# MSP432P401R_Mini_System.net
KiCad netlist of a schematic drawn in Altium Designer
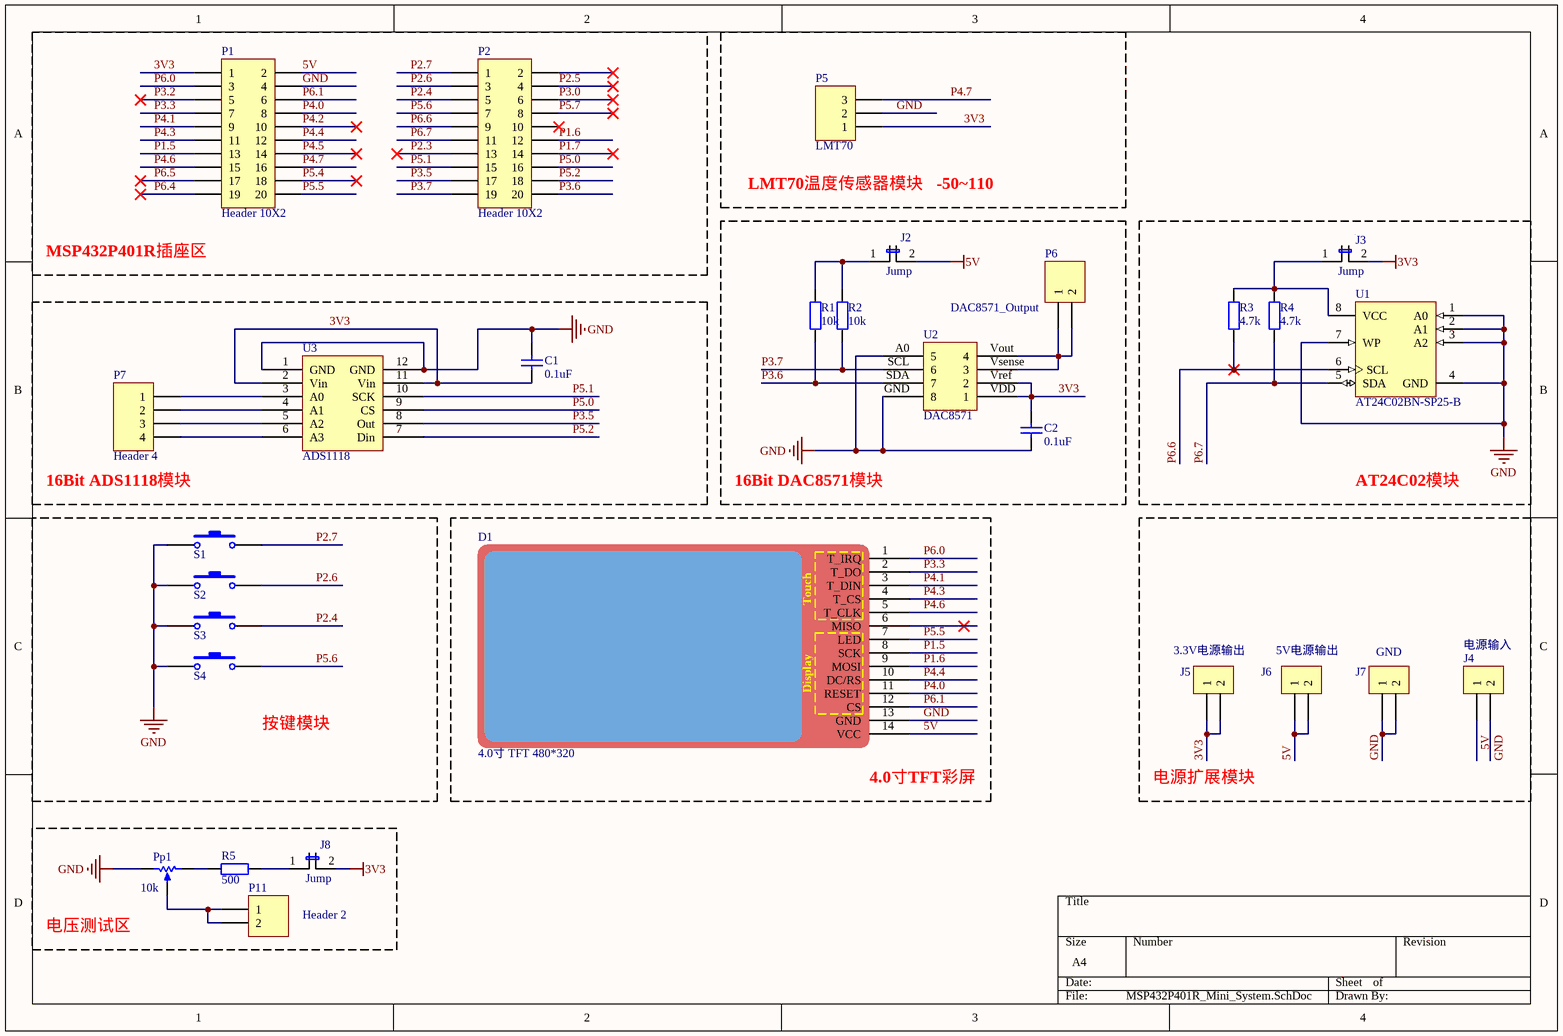
[diagram p0: MSP432P401R_Mini_System.SchDoc]

(export (version "E")
  (design (tool "Eeschema 10.0.6"))
  (components
    (comp (ref "C1")
      (value "0.1uF")
      (footprint "0805_C")
      (description "CBB聚乙烯薄膜电容")
      (fields (field (name "VOLTAGE") "63V") (field (name "PUBLISHER") "Altium Limited"))
      (libsource (lib "02-Miscellaneous_Devices_ZSF_Library") (part "Cap Nicklon"))
    )
    (comp (ref "C2")
      (value "0.1uF")
      (footprint "0805_C")
      (description "CBB聚乙烯薄膜电容")
      (fields (field (name "VOLTAGE") "63V") (field (name "PUBLISHER") "Altium Limited"))
      (libsource (lib "02-Miscellaneous_Devices_ZSF_Library") (part "Cap Nicklon"))
    )
    (comp (ref "D1")
      (value "4.0寸 TFT 480*320")
      (footprint "4.0 TFT")
      (libsource (lib "Mini_System") (part "4.0寸 TFT 480*320"))
    )
    (comp (ref "J2") (value "Jump") (footprint "Jump") (libsource (lib "Mini_System") (part "Jump")))
    (comp (ref "J3") (value "Jump") (footprint "Jump") (libsource (lib "Mini_System") (part "Jump")))
    (comp (ref "J4")
      (value "电源输入")
      (footprint "Connector:XH2.54-2P")
      (description "连接器")
      (libsource (lib "Connector") (part "CON2"))
    )
    (comp (ref "J5")
      (value "3.3V电源输出")
      (footprint "Connector:WJ500V-5.08-2")
      (description "接线端子")
      (libsource (lib "Connector") (part "KF128-5.08MM-2P"))
    )
    (comp (ref "J6")
      (value "5V电源输出")
      (footprint "Connector:WJ500V-5.08-2")
      (description "接线端子")
      (libsource (lib "Connector") (part "KF128-5.08MM-2P"))
    )
    (comp (ref "J7")
      (value "GND")
      (footprint "Connector:WJ500V-5.08-2")
      (description "接线端子")
      (libsource (lib "Connector") (part "KF128-5.08MM-2P"))
    )
    (comp (ref "J8") (value "Jump") (footprint "jump") (libsource (lib "Mini_System") (part "Jump")))
    (comp (ref "P1")
      (value "Header 10X2")
      (footprint "HDR2X10")
      (description "Header, 10-Pin, Dual row")
      (fields (field (name "PUBLISHER") "Altium Limited"))
      (libsource (lib "03-EButterflyIntegratedLibrary") (part "Header 10X2"))
    )
    (comp (ref "P2")
      (value "Header 10X2")
      (footprint "HDR2X10")
      (description "Header, 10-Pin, Dual row")
      (fields (field (name "PUBLISHER") "Altium Limited"))
      (libsource (lib "03-EButterflyIntegratedLibrary") (part "Header 10X2"))
    )
    (comp (ref "P5")
      (value "LMT70")
      (footprint "HDR-1X3_M")
      (description "Header, 3-Pin")
      (fields (field (name "PUBLISHER") "Altium Limited"))
      (libsource (lib "03-EButterflyIntegratedLibrary") (part "Header 3"))
    )
    (comp (ref "P6")
      (value "DAC8571_Output")
      (footprint "HDR-1X2_H")
      (description "Header, 2-Pin")
      (fields (field (name "PUBLISHER") "Altium Limited"))
      (libsource (lib "03-EButterflyIntegratedLibrary") (part "Header 2"))
    )
    (comp (ref "P7")
      (value "Header 4")
      (footprint "HDR1X4")
      (description "Header, 4-Pin")
      (fields (field (name "PUBLISHER") "Altium Limited"))
      (libsource (lib "03-EButterflyIntegratedLibrary") (part "Header 4"))
    )
    (comp (ref "P11")
      (value "Header 2")
      (footprint "HDR1X2")
      (description "Header, 2-Pin")
      (fields (field (name "PUBLISHER") "Altium Limited"))
      (libsource (lib "") (part "Header 2_1"))
    )
    (comp (ref "Pp1")
      (value "10k")
      (footprint "RM065")
      (description "3296电位器")
      (libsource (lib "02-Miscellaneous_Devices_ZSF_Library") (part "RP_3296"))
    )
    (comp (ref "R1")
      (value "10k")
      (footprint "Resistors:0805_R")
      (description "Resistor")
      (fields (field (name "PUBLISHER") "Altium Limited"))
      (libsource (lib "") (part "Res2_1"))
    )
    (comp (ref "R2")
      (value "10k")
      (footprint "Resistors:0805_R")
      (description "Resistor")
      (fields (field (name "PUBLISHER") "Altium Limited"))
      (libsource (lib "") (part "Res2_1"))
    )
    (comp (ref "R3")
      (value "4.7k")
      (footprint "Resistors:0805_R")
      (description "Resistor")
      (fields (field (name "PUBLISHER") "Altium Limited"))
      (libsource (lib "") (part "Res2_1"))
    )
    (comp (ref "R4")
      (value "4.7k")
      (footprint "Resistors:0805_R")
      (description "Resistor")
      (fields (field (name "PUBLISHER") "Altium Limited"))
      (libsource (lib "") (part "Res2_1"))
    )
    (comp (ref "R5")
      (value "500")
      (footprint "Resistors:0805_R")
      (description "Resistor")
      (fields (field (name "PUBLISHER") "Altium Limited"))
      (libsource (lib "Miscellaneous Devices") (part "Res2"))
    )
    (comp (ref "S1")
      (value "S1")
      (footprint "TSW SMD-3*6*4.3")
      (description "Tactile Switch触觉开关")
      (fields (field (name "PUBLISHER") "Altium Limited"))
      (libsource (lib "02-Miscellaneous_Devices_ZSF_Library") (part "SW-PB"))
    )
    (comp (ref "S2")
      (value "S2")
      (footprint "TSW SMD-3*6*4.3")
      (description "Tactile Switch触觉开关")
      (fields (field (name "PUBLISHER") "Altium Limited"))
      (libsource (lib "02-Miscellaneous_Devices_ZSF_Library") (part "SW-PB"))
    )
    (comp (ref "S3")
      (value "S3")
      (footprint "TSW SMD-3*6*4.3")
      (description "Tactile Switch触觉开关")
      (fields (field (name "PUBLISHER") "Altium Limited"))
      (libsource (lib "02-Miscellaneous_Devices_ZSF_Library") (part "SW-PB"))
    )
    (comp (ref "S4")
      (value "S4")
      (footprint "TSW SMD-3*6*4.3")
      (description "Tactile Switch触觉开关")
      (fields (field (name "PUBLISHER") "Altium Limited"))
      (libsource (lib "02-Miscellaneous_Devices_ZSF_Library") (part "SW-PB"))
    )
    (comp (ref "U1")
      (value "AT24C02BN-SP25-B")
      (footprint "DIP8-300_MH")
      (fields (field (name "PUBLISHER") "Altium Limited"))
      (libsource (lib "altium-import") (part "root_0_mirrored_AT24C02BN-SP25-B_"))
    )
    (comp (ref "U2")
      (value "DAC8571")
      (footprint "DIP8-300_MH")
      (description "16位DAC芯片，将数字量转化为模拟电压输出")
      (libsource (lib "Mini_System") (part "DAC8571"))
    )
    (comp (ref "U3")
      (value "ADS1118")
      (footprint "ADS1118")
      (description "16位ADC芯片，将模拟电压信号转化为数字信号供单片机处理")
      (libsource (lib "Mini_System") (part "ADS1118"))
    )
  )
  (nets
    (net (code "1") (name "/P1.5") (class "Default")
      (node (ref "D1") (pin "8") (pinfunction "SCK_8") (pintype "passive"))
      (node (ref "P1") (pin "13") (pinfunction "13_13") (pintype "passive"))
    )
    (net (code "2") (name "/P1.6") (class "Default")
      (node (ref "D1") (pin "9") (pinfunction "MOSI_9") (pintype "passive"))
      (node (ref "P2") (pin "12") (pinfunction "12_12") (pintype "passive"))
    )
    (net (code "3") (name "/P1.7") (class "Default")
      (node (ref "P2") (pin "14") (pinfunction "14_14") (pintype "passive+no_connect"))
    )
    (net (code "4") (name "/P2.3") (class "Default")
      (node (ref "P2") (pin "13") (pinfunction "13_13") (pintype "passive+no_connect"))
    )
    (net (code "5") (name "/P2.4") (class "Default")
      (node (ref "P2") (pin "5") (pinfunction "5_5") (pintype "passive"))
      (node (ref "S3") (pin "2") (pinfunction "2_2") (pintype "passive"))
    )
    (net (code "6") (name "/P2.5") (class "Default")
      (node (ref "P2") (pin "4") (pinfunction "4_4") (pintype "passive+no_connect"))
    )
    (net (code "7") (name "/P2.6") (class "Default")
      (node (ref "P2") (pin "3") (pinfunction "3_3") (pintype "passive"))
      (node (ref "S2") (pin "2") (pinfunction "2_2") (pintype "passive"))
    )
    (net (code "8") (name "/P2.7") (class "Default")
      (node (ref "P2") (pin "1") (pinfunction "1_1") (pintype "passive"))
      (node (ref "S1") (pin "2") (pinfunction "2_2") (pintype "passive"))
    )
    (net (code "9") (name "/P3.0") (class "Default")
      (node (ref "P2") (pin "6") (pinfunction "6_6") (pintype "passive+no_connect"))
    )
    (net (code "10") (name "/P3.2") (class "Default")
      (node (ref "P1") (pin "5") (pinfunction "5_5") (pintype "passive+no_connect"))
    )
    (net (code "11") (name "/P3.3") (class "Default")
      (node (ref "D1") (pin "2") (pinfunction "T_DO_2") (pintype "passive"))
      (node (ref "P1") (pin "7") (pinfunction "7_7") (pintype "passive"))
    )
    (net (code "12") (name "/P3.5") (class "Default")
      (node (ref "P2") (pin "17") (pinfunction "17_17") (pintype "passive"))
      (node (ref "U3") (pin "8") (pinfunction "Out_8") (pintype "passive"))
    )
    (net (code "13") (name "/P3.6") (class "Default")
      (node (ref "P2") (pin "20") (pinfunction "20_20") (pintype "passive"))
      (node (ref "R1") (pin "1") (pinfunction "1_1") (pintype "passive"))
      (node (ref "U2") (pin "SDA") (pinfunction "7_SDA") (pintype "passive"))
    )
    (net (code "14") (name "/P3.7") (class "Default")
      (node (ref "P2") (pin "19") (pinfunction "19_19") (pintype "passive"))
      (node (ref "R2") (pin "1") (pinfunction "1_1") (pintype "passive"))
      (node (ref "U2") (pin "SCL") (pinfunction "6_SCL") (pintype "passive"))
    )
    (net (code "15") (name "/P4.0") (class "Default")
      (node (ref "D1") (pin "11") (pinfunction "RESET_11") (pintype "passive"))
      (node (ref "P1") (pin "8") (pinfunction "8_8") (pintype "passive"))
    )
    (net (code "16") (name "/P4.1") (class "Default")
      (node (ref "D1") (pin "3") (pinfunction "T_DIN_3") (pintype "passive"))
      (node (ref "P1") (pin "9") (pinfunction "9_9") (pintype "passive"))
    )
    (net (code "17") (name "/P4.2") (class "Default")
      (node (ref "P1") (pin "10") (pinfunction "10_10") (pintype "passive+no_connect"))
    )
    (net (code "18") (name "/P4.3") (class "Default")
      (node (ref "D1") (pin "4") (pinfunction "T_CS_4") (pintype "passive"))
      (node (ref "P1") (pin "11") (pinfunction "11_11") (pintype "passive"))
    )
    (net (code "19") (name "/P4.4") (class "Default")
      (node (ref "D1") (pin "10") (pinfunction "DC/RS_10") (pintype "passive"))
      (node (ref "P1") (pin "12") (pinfunction "12_12") (pintype "passive"))
    )
    (net (code "20") (name "/P4.5") (class "Default")
      (node (ref "P1") (pin "14") (pinfunction "14_14") (pintype "passive+no_connect"))
    )
    (net (code "21") (name "/P4.6") (class "Default")
      (node (ref "D1") (pin "5") (pinfunction "T_CLK_5") (pintype "passive"))
      (node (ref "P1") (pin "15") (pinfunction "15_15") (pintype "passive"))
    )
    (net (code "22") (name "/P4.7") (class "Default")
      (node (ref "P1") (pin "16") (pinfunction "16_16") (pintype "passive"))
      (node (ref "P5") (pin "3") (pinfunction "3_3") (pintype "passive"))
    )
    (net (code "23") (name "/P5.0") (class "Default")
      (node (ref "P2") (pin "16") (pinfunction "16_16") (pintype "passive"))
      (node (ref "U3") (pin "9") (pinfunction "CS_9") (pintype "passive"))
    )
    (net (code "24") (name "/P5.1") (class "Default")
      (node (ref "P2") (pin "15") (pinfunction "15_15") (pintype "passive"))
      (node (ref "U3") (pin "10") (pinfunction "SCK_10") (pintype "passive"))
    )
    (net (code "25") (name "/P5.2") (class "Default")
      (node (ref "P2") (pin "18") (pinfunction "18_18") (pintype "passive"))
      (node (ref "U3") (pin "7") (pinfunction "Din_7") (pintype "passive"))
    )
    (net (code "26") (name "/P5.4") (class "Default")
      (node (ref "P1") (pin "18") (pinfunction "18_18") (pintype "passive+no_connect"))
    )
    (net (code "27") (name "/P5.5") (class "Default")
      (node (ref "D1") (pin "7") (pinfunction "LED_7") (pintype "passive"))
      (node (ref "P1") (pin "20") (pinfunction "20_20") (pintype "passive"))
    )
    (net (code "28") (name "/P5.6") (class "Default")
      (node (ref "P2") (pin "7") (pinfunction "7_7") (pintype "passive"))
      (node (ref "S4") (pin "2") (pinfunction "2_2") (pintype "passive"))
    )
    (net (code "29") (name "/P5.7") (class "Default")
      (node (ref "P2") (pin "8") (pinfunction "8_8") (pintype "passive+no_connect"))
    )
    (net (code "30") (name "/P6.0") (class "Default")
      (node (ref "D1") (pin "1") (pinfunction "T_IRQ_1") (pintype "passive"))
      (node (ref "P1") (pin "3") (pinfunction "3_3") (pintype "passive"))
    )
    (net (code "31") (name "/P6.1") (class "Default")
      (node (ref "D1") (pin "12") (pinfunction "CS_12") (pintype "passive"))
      (node (ref "P1") (pin "6") (pinfunction "6_6") (pintype "passive"))
    )
    (net (code "32") (name "/P6.4") (class "Default")
      (node (ref "P1") (pin "19") (pinfunction "19_19") (pintype "passive+no_connect"))
    )
    (net (code "33") (name "/P6.5") (class "Default")
      (node (ref "P1") (pin "17") (pinfunction "17_17") (pintype "passive+no_connect"))
    )
    (net (code "34") (name "/P6.6") (class "Default")
      (node (ref "P2") (pin "9") (pinfunction "9_9") (pintype "passive"))
      (node (ref "R3") (pin "1") (pinfunction "1_1") (pintype "passive"))
      (node (ref "U1") (pin "6") (pinfunction "SCL_6") (pintype "input"))
    )
    (net (code "35") (name "/P6.7") (class "Default")
      (node (ref "P2") (pin "11") (pinfunction "11_11") (pintype "passive"))
      (node (ref "R4") (pin "1") (pinfunction "1_1") (pintype "passive"))
      (node (ref "U1") (pin "5") (pinfunction "SDA_5") (pintype "bidirectional"))
    )
    (net (code "36") (name "3V3") (class "Default")
      (node (ref "C1") (pin "1") (pinfunction "1_1") (pintype "passive"))
      (node (ref "C2") (pin "2") (pinfunction "2_2") (pintype "passive"))
      (node (ref "J3") (pin "2") (pinfunction "2_2") (pintype "passive"))
      (node (ref "J5") (pin "1") (pinfunction "1_1") (pintype "passive"))
      (node (ref "J5") (pin "2") (pinfunction "2_2") (pintype "passive"))
      (node (ref "J8") (pin "2") (pinfunction "2_2") (pintype "passive"))
      (node (ref "P1") (pin "1") (pinfunction "1_1") (pintype "passive"))
      (node (ref "P5") (pin "1") (pinfunction "1_1") (pintype "passive"))
      (node (ref "U2") (pin "VDD") (pinfunction "1_VDD") (pintype "passive"))
      (node (ref "U2") (pin "Vref") (pinfunction "2_Vref") (pintype "passive"))
      (node (ref "U3") (pin "11") (pinfunction "Vin_11") (pintype "passive"))
      (node (ref "U3") (pin "2") (pinfunction "Vin_2") (pintype "passive"))
    )
    (net (code "37") (name "5V") (class "Default")
      (node (ref "D1") (pin "14") (pinfunction "VCC_14") (pintype "passive"))
      (node (ref "J2") (pin "2") (pinfunction "2_2") (pintype "passive"))
      (node (ref "J4") (pin "1") (pinfunction "1_1") (pintype "passive"))
      (node (ref "J6") (pin "1") (pinfunction "1_1") (pintype "passive"))
      (node (ref "J6") (pin "2") (pinfunction "2_2") (pintype "passive"))
      (node (ref "P1") (pin "2") (pinfunction "2_2") (pintype "passive"))
    )
    (net (code "38") (name "GND") (class "Default")
      (node (ref "C1") (pin "2") (pinfunction "2_2") (pintype "passive"))
      (node (ref "C2") (pin "1") (pinfunction "1_1") (pintype "passive"))
      (node (ref "D1") (pin "13") (pinfunction "GND_13") (pintype "passive"))
      (node (ref "J4") (pin "2") (pinfunction "2_2") (pintype "passive"))
      (node (ref "J7") (pin "1") (pinfunction "1_1") (pintype "passive"))
      (node (ref "J7") (pin "2") (pinfunction "2_2") (pintype "passive"))
      (node (ref "P1") (pin "4") (pinfunction "4_4") (pintype "passive"))
      (node (ref "P5") (pin "2") (pinfunction "2_2") (pintype "passive"))
      (node (ref "Pp1") (pin "3") (pinfunction "BOT_3") (pintype "passive"))
      (node (ref "S1") (pin "1") (pinfunction "1_1") (pintype "passive"))
      (node (ref "S2") (pin "1") (pinfunction "1_1") (pintype "passive"))
      (node (ref "S3") (pin "1") (pinfunction "1_1") (pintype "passive"))
      (node (ref "S4") (pin "1") (pinfunction "1_1") (pintype "passive"))
      (node (ref "U1") (pin "1") (pinfunction "A0_1") (pintype "input"))
      (node (ref "U1") (pin "2") (pinfunction "A1_2") (pintype "input"))
      (node (ref "U1") (pin "3") (pinfunction "A2_3") (pintype "input"))
      (node (ref "U1") (pin "4") (pinfunction "GND_4") (pintype "power_in"))
      (node (ref "U1") (pin "7") (pinfunction "WP_7") (pintype "input"))
      (node (ref "U2") (pin "A0") (pinfunction "5_A0") (pintype "passive"))
      (node (ref "U2") (pin "GND") (pinfunction "8_GND") (pintype "passive"))
      (node (ref "U3") (pin "1") (pinfunction "GND_1") (pintype "passive"))
      (node (ref "U3") (pin "12") (pinfunction "GND_12") (pintype "passive"))
    )
    (net (code "39") (name "Net-(J2-Pad1)") (class "Default")
      (node (ref "J2") (pin "1") (pinfunction "1_1") (pintype "passive"))
      (node (ref "R1") (pin "2") (pinfunction "2_2") (pintype "passive"))
      (node (ref "R2") (pin "2") (pinfunction "2_2") (pintype "passive"))
    )
    (net (code "40") (name "Net-(J8-Pad1)") (class "Default")
      (node (ref "J8") (pin "1") (pinfunction "1_1") (pintype "passive"))
      (node (ref "R5") (pin "1") (pinfunction "1_1") (pintype "passive"))
    )
    (net (code "41") (name "Net-(Pp1-TAP)") (class "Default")
      (node (ref "P11") (pin "1") (pinfunction "1_1") (pintype "passive"))
      (node (ref "P11") (pin "2") (pinfunction "2_2") (pintype "passive"))
      (node (ref "Pp1") (pin "2") (pinfunction "TAP_2") (pintype "passive"))
    )
    (net (code "42") (name "Net-(Pp1-TOP)") (class "Default")
      (node (ref "Pp1") (pin "1") (pinfunction "TOP_1") (pintype "passive"))
      (node (ref "R5") (pin "2") (pinfunction "2_2") (pintype "passive"))
    )
    (net (code "43") (name "Net-(U1-VCC)") (class "Default")
      (node (ref "J3") (pin "1") (pinfunction "1_1") (pintype "passive"))
      (node (ref "R3") (pin "2") (pinfunction "2_2") (pintype "passive"))
      (node (ref "R4") (pin "2") (pinfunction "2_2") (pintype "passive"))
      (node (ref "U1") (pin "8") (pinfunction "VCC_8") (pintype "power_in"))
    )
    (net (code "44") (name "Net-(U2-3)") (class "Default")
      (node (ref "P6") (pin "1") (pinfunction "1_1") (pintype "passive"))
      (node (ref "P6") (pin "2") (pinfunction "2_2") (pintype "passive"))
      (node (ref "U2") (pin "Vout") (pinfunction "4_Vout") (pintype "passive"))
      (node (ref "U2") (pin "Vsense") (pinfunction "3_Vsense") (pintype "passive"))
    )
    (net (code "45") (name "Net-(U3-A0)") (class "Default")
      (node (ref "P7") (pin "1") (pinfunction "1_1") (pintype "passive"))
      (node (ref "U3") (pin "3") (pinfunction "A0_3") (pintype "passive"))
    )
    (net (code "46") (name "Net-(U3-A1)") (class "Default")
      (node (ref "P7") (pin "2") (pinfunction "2_2") (pintype "passive"))
      (node (ref "U3") (pin "4") (pinfunction "A1_4") (pintype "passive"))
    )
    (net (code "47") (name "Net-(U3-A2)") (class "Default")
      (node (ref "P7") (pin "3") (pinfunction "3_3") (pintype "passive"))
      (node (ref "U3") (pin "5") (pinfunction "A2_5") (pintype "passive"))
    )
    (net (code "48") (name "Net-(U3-A3)") (class "Default")
      (node (ref "P7") (pin "4") (pinfunction "4_4") (pintype "passive"))
      (node (ref "U3") (pin "6") (pinfunction "A3_6") (pintype "passive"))
    )
    (net (code "49") (name "unconnected-(D1-MISO-Pad6)") (class "Default")
      (node (ref "D1") (pin "6") (pinfunction "MISO_6") (pintype "passive"))
    )
    (net (code "50") (name "unconnected-(P2-Pad2)") (class "Default")
      (node (ref "P2") (pin "2") (pinfunction "2_2") (pintype "passive+no_connect"))
    )
    (net (code "51") (name "unconnected-(P2-Pad10)") (class "Default")
      (node (ref "P2") (pin "10") (pinfunction "10_10") (pintype "passive+no_connect"))
    )
  )
)
